# Shruthi-Analog-SMR4-mkII-v02.net
KiCad netlist of a schematic drawn in EAGLE
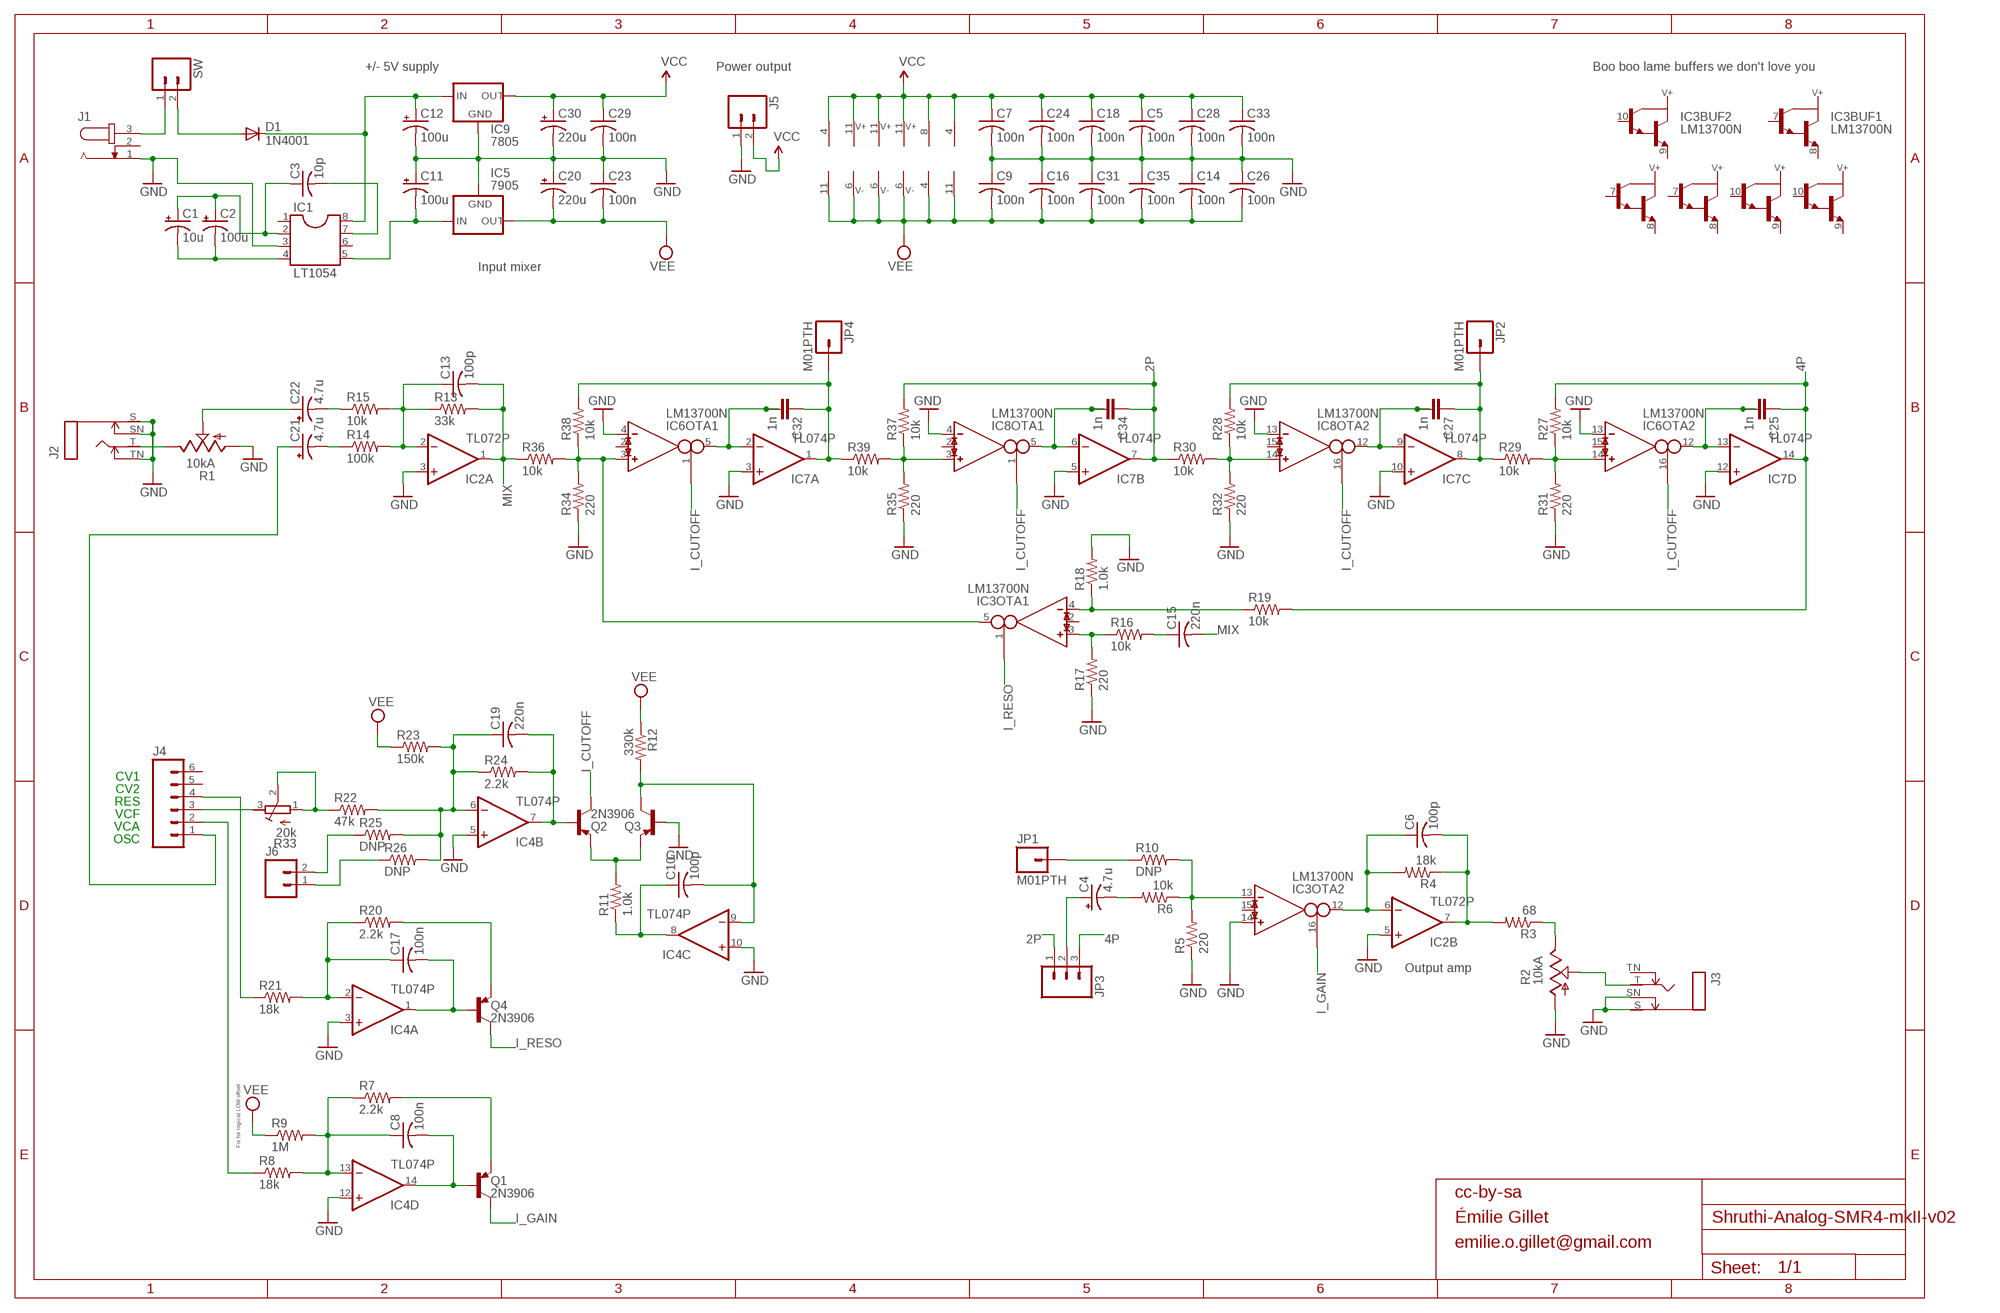
[diagram p0: schematic, sheet 1]

(export (version "E")
  (design (tool "Eeschema 10.0.6"))
  (components
    (comp (ref "C1")
      (value "10u")
      (footprint "eagle-import:E2,5-5")
      (libsource (lib "eagle-import") (part "CPOL-USE2.5-5"))
    )
    (comp (ref "C2")
      (value "100u")
      (footprint "eagle-import:E2,5-6")
      (libsource (lib "eagle-import") (part "CPOL-USE2.5-6"))
    )
    (comp (ref "C3")
      (value "10p")
      (footprint "eagle-import:C025-025X050")
      (libsource (lib "eagle-import") (part "C-US025-025X050"))
    )
    (comp (ref "C4")
      (value "4.7u")
      (footprint "eagle-import:E2,5-6")
      (libsource (lib "eagle-import") (part "CPOL-USE2.5-6"))
    )
    (comp (ref "C5")
      (value "100n")
      (footprint "eagle-import:C025-025X050")
      (libsource (lib "eagle-import") (part "C-US025-025X050"))
    )
    (comp (ref "C6")
      (value "100p")
      (footprint "eagle-import:C025-025X050")
      (libsource (lib "eagle-import") (part "C-US025-025X050"))
    )
    (comp (ref "C7")
      (value "100n")
      (footprint "eagle-import:C025-025X050")
      (libsource (lib "eagle-import") (part "C-US025-025X050"))
    )
    (comp (ref "C8")
      (value "100n")
      (footprint "eagle-import:C025-025X050")
      (libsource (lib "eagle-import") (part "C-US025-025X050"))
    )
    (comp (ref "C9")
      (value "100n")
      (footprint "eagle-import:C025-025X050")
      (libsource (lib "eagle-import") (part "C-US025-025X050"))
    )
    (comp (ref "C10")
      (value "100p")
      (footprint "eagle-import:C025-025X050")
      (libsource (lib "eagle-import") (part "C-US025-025X050"))
    )
    (comp (ref "C11")
      (value "100u")
      (footprint "eagle-import:E2,5-7")
      (libsource (lib "eagle-import") (part "CPOL-USE2.5-7"))
    )
    (comp (ref "C12")
      (value "100u")
      (footprint "eagle-import:E2,5-7")
      (libsource (lib "eagle-import") (part "CPOL-USE2.5-7"))
    )
    (comp (ref "C13")
      (value "100p")
      (footprint "eagle-import:C025-025X050")
      (libsource (lib "eagle-import") (part "C-US025-025X050"))
    )
    (comp (ref "C14")
      (value "100n")
      (footprint "eagle-import:C025-025X050")
      (libsource (lib "eagle-import") (part "C-US025-025X050"))
    )
    (comp (ref "C15")
      (value "220n")
      (footprint "eagle-import:C025-025X050")
      (libsource (lib "eagle-import") (part "C-US025-025X050"))
    )
    (comp (ref "C16")
      (value "100n")
      (footprint "eagle-import:C025-025X050")
      (libsource (lib "eagle-import") (part "C-US025-025X050"))
    )
    (comp (ref "C17")
      (value "100n")
      (footprint "eagle-import:C025-025X050")
      (libsource (lib "eagle-import") (part "C-US025-025X050"))
    )
    (comp (ref "C18")
      (value "100n")
      (footprint "eagle-import:C025-025X050")
      (libsource (lib "eagle-import") (part "C-US025-025X050"))
    )
    (comp (ref "C19")
      (value "220n")
      (footprint "eagle-import:C025-025X050")
      (libsource (lib "eagle-import") (part "C-US025-025X050"))
    )
    (comp (ref "C20")
      (value "220u")
      (footprint "eagle-import:E5-10,5")
      (libsource (lib "eagle-import") (part "CPOL-USE5-10.5"))
    )
    (comp (ref "C21")
      (value "4.7u")
      (footprint "eagle-import:E2,5-6")
      (libsource (lib "eagle-import") (part "CPOL-USE2.5-6"))
    )
    (comp (ref "C22")
      (value "4.7u")
      (footprint "eagle-import:E2,5-6")
      (libsource (lib "eagle-import") (part "CPOL-USE2.5-6"))
    )
    (comp (ref "C23")
      (value "100n")
      (footprint "eagle-import:C025-025X050")
      (libsource (lib "eagle-import") (part "C-US025-025X050"))
    )
    (comp (ref "C24")
      (value "100n")
      (footprint "eagle-import:C025-025X050")
      (libsource (lib "eagle-import") (part "C-US025-025X050"))
    )
    (comp (ref "C25")
      (value "1n")
      (footprint "eagle-import:C2.5_5-2")
      (libsource (lib "eagle-import") (part "C-2.5-5/2"))
    )
    (comp (ref "C26")
      (value "100n")
      (footprint "eagle-import:C025-025X050")
      (libsource (lib "eagle-import") (part "C-US025-025X050"))
    )
    (comp (ref "C27")
      (value "1n")
      (footprint "eagle-import:C2.5_5-2")
      (libsource (lib "eagle-import") (part "C-2.5-5/2"))
    )
    (comp (ref "C28")
      (value "100n")
      (footprint "eagle-import:C025-025X050")
      (libsource (lib "eagle-import") (part "C-US025-025X050"))
    )
    (comp (ref "C29")
      (value "100n")
      (footprint "eagle-import:C025-025X050")
      (libsource (lib "eagle-import") (part "C-US025-025X050"))
    )
    (comp (ref "C30")
      (value "220u")
      (footprint "eagle-import:E5-10,5")
      (libsource (lib "eagle-import") (part "CPOL-USE5-10.5"))
    )
    (comp (ref "C31")
      (value "100n")
      (footprint "eagle-import:C025-025X050")
      (libsource (lib "eagle-import") (part "C-US025-025X050"))
    )
    (comp (ref "C32")
      (value "1n")
      (footprint "eagle-import:C2.5_5-2")
      (libsource (lib "eagle-import") (part "C-2.5-5/2"))
    )
    (comp (ref "C33")
      (value "100n")
      (footprint "eagle-import:C025-025X050")
      (libsource (lib "eagle-import") (part "C-US025-025X050"))
    )
    (comp (ref "C34")
      (value "1n")
      (footprint "eagle-import:C2.5_5-2")
      (libsource (lib "eagle-import") (part "C-2.5-5/2"))
    )
    (comp (ref "C35")
      (value "100n")
      (footprint "eagle-import:C025-025X050")
      (libsource (lib "eagle-import") (part "C-US025-025X050"))
    )
    (comp (ref "D1")
      (value "1N4001")
      (footprint "eagle-import:DO41-10")
      (libsource (lib "eagle-import") (part "1N4004"))
    )
    (comp (ref "IC1")
      (value "LT1054")
      (footprint "eagle-import:DIL08")
      (libsource (lib "eagle-import") (part "DIL8"))
    )
    (comp (ref "IC2")
      (value "TL072P")
      (footprint "eagle-import:DIL08")
      (libsource (lib "eagle-import") (part "TL072P"))
    )
    (comp (ref "IC3")
      (value "LM13700N")
      (footprint "eagle-import:DIL16")
      (libsource (lib "eagle-import") (part "LM13700N"))
    )
    (comp (ref "IC4")
      (value "TL074P")
      (footprint "eagle-import:DIL14")
      (libsource (lib "eagle-import") (part "TL084P"))
    )
    (comp (ref "IC5")
      (value "7905")
      (footprint "eagle-import:79XXS")
      (libsource (lib "eagle-import") (part "79XXS"))
    )
    (comp (ref "IC6")
      (value "LM13700N")
      (footprint "eagle-import:DIL16")
      (libsource (lib "eagle-import") (part "LM13700N"))
    )
    (comp (ref "IC7")
      (value "TL074P")
      (footprint "eagle-import:DIL14")
      (libsource (lib "eagle-import") (part "TL084P"))
    )
    (comp (ref "IC8")
      (value "LM13700N")
      (footprint "eagle-import:DIL16")
      (libsource (lib "eagle-import") (part "LM13700N"))
    )
    (comp (ref "IC9")
      (value "7805")
      (footprint "eagle-import:78XXS")
      (libsource (lib "eagle-import") (part "78XXS"))
    )
    (comp (ref "J1")
      (value "JACK-PLUG2")
      (footprint "eagle-import:SPC4078_BIG_HOLES")
      (libsource (lib "eagle-import") (part "JACK-PLUG2"))
    )
    (comp (ref "J2")
      (value "MONOSWS")
      (footprint "eagle-import:NMJ4HC-S")
      (libsource (lib "eagle-import") (part "MONOSWS"))
    )
    (comp (ref "J3")
      (value "MONOSWS")
      (footprint "eagle-import:NMJ4HC-S")
      (libsource (lib "eagle-import") (part "MONOSWS"))
    )
    (comp (ref "J4")
      (value "M06SIP")
      (footprint "eagle-import:1X06")
      (libsource (lib "eagle-import") (part "M06SIP"))
    )
    (comp (ref "J5")
      (value "M02PTH")
      (footprint "eagle-import:1X02")
      (libsource (lib "eagle-import") (part "M02PTH"))
    )
    (comp (ref "J6")
      (value "M02PTH")
      (footprint "eagle-import:1X02")
      (libsource (lib "eagle-import") (part "M02PTH"))
    )
    (comp (ref "JP1")
      (value "M01PTH")
      (footprint "eagle-import:1X01")
      (libsource (lib "eagle-import") (part "M01PTH"))
    )
    (comp (ref "JP2")
      (value "M01PTH")
      (footprint "eagle-import:1X01")
      (libsource (lib "eagle-import") (part "M01PTH"))
    )
    (comp (ref "JP3")
      (value "M03PTH")
      (footprint "eagle-import:1X03")
      (libsource (lib "eagle-import") (part "M03PTH"))
    )
    (comp (ref "JP4")
      (value "M01PTH")
      (footprint "eagle-import:1X01")
      (libsource (lib "eagle-import") (part "M01PTH"))
    )
    (comp (ref "Q1")
      (value "2N3906")
      (footprint "eagle-import:TO92-")
      (libsource (lib "eagle-import") (part "2N3906-"))
    )
    (comp (ref "Q2")
      (value "2N3906")
      (footprint "eagle-import:TO92-")
      (libsource (lib "eagle-import") (part "2N3906-"))
    )
    (comp (ref "Q3")
      (value "2N3906")
      (footprint "eagle-import:TO92-")
      (libsource (lib "eagle-import") (part "2N3906-"))
    )
    (comp (ref "Q4")
      (value "2N3906")
      (footprint "eagle-import:TO92-")
      (libsource (lib "eagle-import") (part "2N3906-"))
    )
    (comp (ref "R1")
      (value "10kA")
      (footprint "eagle-import:CABLE_POT_6MM")
      (libsource (lib "eagle-import") (part "POT_USCABLED"))
    )
    (comp (ref "R2")
      (value "10kA")
      (footprint "eagle-import:CABLE_POT_6MM")
      (libsource (lib "eagle-import") (part "POT_USCABLED"))
    )
    (comp (ref "R3")
      (value "68")
      (footprint "eagle-import:0204_7")
      (libsource (lib "eagle-import") (part "R-US_0204/7"))
    )
    (comp (ref "R4")
      (value "18k")
      (footprint "eagle-import:0204_7")
      (libsource (lib "eagle-import") (part "R-US_0204/7"))
    )
    (comp (ref "R5")
      (value "220")
      (footprint "eagle-import:0204_7")
      (libsource (lib "eagle-import") (part "R-US_0204/7"))
    )
    (comp (ref "R6")
      (value "10k")
      (footprint "eagle-import:0204_7")
      (libsource (lib "eagle-import") (part "R-US_0204/7"))
    )
    (comp (ref "R7")
      (value "2.2k")
      (footprint "eagle-import:0204_7")
      (libsource (lib "eagle-import") (part "R-US_0204/7"))
    )
    (comp (ref "R8")
      (value "18k")
      (footprint "eagle-import:0204_7")
      (libsource (lib "eagle-import") (part "R-US_0204/7"))
    )
    (comp (ref "R9")
      (value "1M")
      (footprint "eagle-import:0204_7")
      (libsource (lib "eagle-import") (part "R-US_0204/7"))
    )
    (comp (ref "R10")
      (value "DNP")
      (footprint "eagle-import:0204V")
      (libsource (lib "eagle-import") (part "R-US_0204/2V"))
    )
    (comp (ref "R11")
      (value "1.0k")
      (footprint "eagle-import:0204_7")
      (libsource (lib "eagle-import") (part "R-US_0204/7"))
    )
    (comp (ref "R12")
      (value "330k")
      (footprint "eagle-import:0204_7")
      (libsource (lib "eagle-import") (part "R-US_0204/7"))
    )
    (comp (ref "R13")
      (value "33k")
      (footprint "eagle-import:0204_7")
      (libsource (lib "eagle-import") (part "R-US_0204/7"))
    )
    (comp (ref "R14")
      (value "100k")
      (footprint "eagle-import:0204_7")
      (libsource (lib "eagle-import") (part "R-US_0204/7"))
    )
    (comp (ref "R15")
      (value "10k")
      (footprint "eagle-import:0204_7")
      (libsource (lib "eagle-import") (part "R-US_0204/7"))
    )
    (comp (ref "R16")
      (value "10k")
      (footprint "eagle-import:0204_7")
      (libsource (lib "eagle-import") (part "R-US_0204/7"))
    )
    (comp (ref "R17")
      (value "220")
      (footprint "eagle-import:0204_7")
      (libsource (lib "eagle-import") (part "R-US_0204/7"))
    )
    (comp (ref "R18")
      (value "1.0k")
      (footprint "eagle-import:0204_7")
      (libsource (lib "eagle-import") (part "R-US_0204/7"))
    )
    (comp (ref "R19")
      (value "10k")
      (footprint "eagle-import:0204_7")
      (libsource (lib "eagle-import") (part "R-US_0204/7"))
    )
    (comp (ref "R20")
      (value "2.2k")
      (footprint "eagle-import:0204_7")
      (libsource (lib "eagle-import") (part "R-US_0204/7"))
    )
    (comp (ref "R21")
      (value "18k")
      (footprint "eagle-import:0204_7")
      (libsource (lib "eagle-import") (part "R-US_0204/7"))
    )
    (comp (ref "R22")
      (value "47k")
      (footprint "eagle-import:0204_7")
      (libsource (lib "eagle-import") (part "R-US_0204/7"))
    )
    (comp (ref "R23")
      (value "150k")
      (footprint "eagle-import:0204_7")
      (libsource (lib "eagle-import") (part "R-US_0204/7"))
    )
    (comp (ref "R24")
      (value "2.2k")
      (footprint "eagle-import:0204_7")
      (libsource (lib "eagle-import") (part "R-US_0204/7"))
    )
    (comp (ref "R25")
      (value "DNP")
      (footprint "eagle-import:0204V")
      (libsource (lib "eagle-import") (part "R-US_0204/2V"))
    )
    (comp (ref "R26")
      (value "DNP")
      (footprint "eagle-import:0204V")
      (libsource (lib "eagle-import") (part "R-US_0204/2V"))
    )
    (comp (ref "R27")
      (value "10k")
      (footprint "eagle-import:0204_7")
      (libsource (lib "eagle-import") (part "R-US_0204/7"))
    )
    (comp (ref "R28")
      (value "10k")
      (footprint "eagle-import:0204_7")
      (libsource (lib "eagle-import") (part "R-US_0204/7"))
    )
    (comp (ref "R29")
      (value "10k")
      (footprint "eagle-import:0204_7")
      (libsource (lib "eagle-import") (part "R-US_0204/7"))
    )
    (comp (ref "R30")
      (value "10k")
      (footprint "eagle-import:0204_7")
      (libsource (lib "eagle-import") (part "R-US_0204/7"))
    )
    (comp (ref "R31")
      (value "220")
      (footprint "eagle-import:0204_7")
      (libsource (lib "eagle-import") (part "R-US_0204/7"))
    )
    (comp (ref "R32")
      (value "220")
      (footprint "eagle-import:0204_7")
      (libsource (lib "eagle-import") (part "R-US_0204/7"))
    )
    (comp (ref "R33")
      (value "20k")
      (footprint "eagle-import:RTRIM3296X")
      (libsource (lib "eagle-import") (part "R-TRIMM3296X"))
    )
    (comp (ref "R34")
      (value "220")
      (footprint "eagle-import:0204_7")
      (libsource (lib "eagle-import") (part "R-US_0204/7"))
    )
    (comp (ref "R35")
      (value "220")
      (footprint "eagle-import:0204_7")
      (libsource (lib "eagle-import") (part "R-US_0204/7"))
    )
    (comp (ref "R36")
      (value "10k")
      (footprint "eagle-import:0204_7")
      (libsource (lib "eagle-import") (part "R-US_0204/7"))
    )
    (comp (ref "R37")
      (value "10k")
      (footprint "eagle-import:0204_7")
      (libsource (lib "eagle-import") (part "R-US_0204/7"))
    )
    (comp (ref "R38")
      (value "10k")
      (footprint "eagle-import:0204_7")
      (libsource (lib "eagle-import") (part "R-US_0204/7"))
    )
    (comp (ref "R39")
      (value "10k")
      (footprint "eagle-import:0204_7")
      (libsource (lib "eagle-import") (part "R-US_0204/7"))
    )
    (comp (ref "SW")
      (value "M02PTH")
      (footprint "eagle-import:1X02")
      (libsource (lib "eagle-import") (part "M02PTH"))
    )
  )
  (nets
    (net (code "1") (name "/2P") (class "Default")
      (node (ref "C34") (pin "1") (pinfunction "1_1") (pintype "passive"))
      (node (ref "IC7") (pin "7") (pinfunction "OUT_7") (pintype "output"))
      (node (ref "JP3") (pin "1") (pinfunction "1_1") (pintype "passive"))
      (node (ref "R30") (pin "1") (pinfunction "1_1") (pintype "passive"))
      (node (ref "R37") (pin "2") (pinfunction "2_2") (pintype "passive"))
    )
    (net (code "2") (name "/4P") (class "Default")
      (node (ref "C25") (pin "1") (pinfunction "1_1") (pintype "passive"))
      (node (ref "IC7") (pin "14") (pinfunction "OUT_14") (pintype "output"))
      (node (ref "JP3") (pin "3") (pinfunction "3_3") (pintype "passive"))
      (node (ref "R19") (pin "2") (pinfunction "2_2") (pintype "passive"))
      (node (ref "R27") (pin "2") (pinfunction "2_2") (pintype "passive"))
    )
    (net (code "3") (name "/I_CUTOFF") (class "Default")
      (node (ref "IC6") (pin "1") (pinfunction "I_BIAS_1") (pintype "input"))
      (node (ref "IC6") (pin "16") (pinfunction "I_BIAS_16") (pintype "input"))
      (node (ref "IC8") (pin "1") (pinfunction "I_BIAS_1") (pintype "input"))
      (node (ref "IC8") (pin "16") (pinfunction "I_BIAS_16") (pintype "input"))
      (node (ref "Q2") (pin "1") (pinfunction "C_1") (pintype "passive"))
    )
    (net (code "4") (name "/I_GAIN") (class "Default")
      (node (ref "IC3") (pin "16") (pinfunction "I_BIAS_16") (pintype "input"))
      (node (ref "Q1") (pin "1") (pinfunction "C_1") (pintype "passive"))
    )
    (net (code "5") (name "/I_RESO") (class "Default")
      (node (ref "IC3") (pin "1") (pinfunction "I_BIAS_1") (pintype "input"))
      (node (ref "Q4") (pin "1") (pinfunction "C_1") (pintype "passive"))
    )
    (net (code "6") (name "/MIX") (class "Default")
      (node (ref "C13") (pin "2") (pinfunction "2_2") (pintype "passive"))
      (node (ref "C15") (pin "2") (pinfunction "2_2") (pintype "passive"))
      (node (ref "IC2") (pin "1") (pinfunction "OUT_1") (pintype "output"))
      (node (ref "R13") (pin "2") (pinfunction "2_2") (pintype "passive"))
      (node (ref "R36") (pin "1") (pinfunction "1_1") (pintype "passive"))
    )
    (net (code "7") (name "GND") (class "Default")
      (node (ref "C11") (pin "+") (pinfunction "+_+") (pintype "passive"))
      (node (ref "C12") (pin "-") (pinfunction "-_-") (pintype "passive"))
      (node (ref "C14") (pin "1") (pinfunction "1_1") (pintype "passive"))
      (node (ref "C16") (pin "1") (pinfunction "1_1") (pintype "passive"))
      (node (ref "C18") (pin "2") (pinfunction "2_2") (pintype "passive"))
      (node (ref "C20") (pin "+") (pinfunction "+_+") (pintype "passive"))
      (node (ref "C23") (pin "1") (pinfunction "1_1") (pintype "passive"))
      (node (ref "C24") (pin "2") (pinfunction "2_2") (pintype "passive"))
      (node (ref "C26") (pin "1") (pinfunction "1_1") (pintype "passive"))
      (node (ref "C28") (pin "2") (pinfunction "2_2") (pintype "passive"))
      (node (ref "C29") (pin "2") (pinfunction "2_2") (pintype "passive"))
      (node (ref "C30") (pin "-") (pinfunction "-_-") (pintype "passive"))
      (node (ref "C31") (pin "1") (pinfunction "1_1") (pintype "passive"))
      (node (ref "C33") (pin "2") (pinfunction "2_2") (pintype "passive"))
      (node (ref "C35") (pin "1") (pinfunction "1_1") (pintype "passive"))
      (node (ref "C5") (pin "2") (pinfunction "2_2") (pintype "passive"))
      (node (ref "C7") (pin "2") (pinfunction "2_2") (pintype "passive"))
      (node (ref "C9") (pin "1") (pinfunction "1_1") (pintype "passive"))
      (node (ref "IC1") (pin "3") (pinfunction "3_3") (pintype "passive"))
      (node (ref "IC2") (pin "3") (pinfunction "+IN_3") (pintype "input"))
      (node (ref "IC2") (pin "5") (pinfunction "+IN_5") (pintype "input"))
      (node (ref "IC3") (pin "14") (pinfunction "IN_P_14") (pintype "input"))
      (node (ref "IC4") (pin "10") (pinfunction "+IN_10") (pintype "input"))
      (node (ref "IC4") (pin "12") (pinfunction "+IN_12") (pintype "input"))
      (node (ref "IC4") (pin "3") (pinfunction "+IN_3") (pintype "input"))
      (node (ref "IC4") (pin "5") (pinfunction "+IN_5") (pintype "input"))
      (node (ref "IC5") (pin "GND") (pinfunction "GND_GND") (pintype "input"))
      (node (ref "IC6") (pin "13") (pinfunction "IN_N_13") (pintype "input"))
      (node (ref "IC6") (pin "4") (pinfunction "IN_N_4") (pintype "input"))
      (node (ref "IC7") (pin "10") (pinfunction "+IN_10") (pintype "input"))
      (node (ref "IC7") (pin "12") (pinfunction "+IN_12") (pintype "input"))
      (node (ref "IC7") (pin "3") (pinfunction "+IN_3") (pintype "input"))
      (node (ref "IC7") (pin "5") (pinfunction "+IN_5") (pintype "input"))
      (node (ref "IC8") (pin "13") (pinfunction "IN_N_13") (pintype "input"))
      (node (ref "IC8") (pin "4") (pinfunction "IN_N_4") (pintype "input"))
      (node (ref "IC9") (pin "GND") (pinfunction "GND_GND") (pintype "input"))
      (node (ref "J1") (pin "1") (pinfunction "1_1") (pintype "passive"))
      (node (ref "J2") (pin "S") (pinfunction "S_S") (pintype "passive"))
      (node (ref "J2") (pin "SN") (pinfunction "SN_SN") (pintype "passive"))
      (node (ref "J2") (pin "TN") (pinfunction "TN_TN") (pintype "passive"))
      (node (ref "J3") (pin "S") (pinfunction "S_S") (pintype "passive"))
      (node (ref "J3") (pin "SN") (pinfunction "SN_SN") (pintype "passive"))
      (node (ref "J5") (pin "1") (pinfunction "1_1") (pintype "passive"))
      (node (ref "Q3") (pin "2") (pinfunction "B_2") (pintype "passive"))
      (node (ref "R1") (pin "A") (pinfunction "A_A") (pintype "passive"))
      (node (ref "R17") (pin "1") (pinfunction "1_1") (pintype "passive"))
      (node (ref "R18") (pin "2") (pinfunction "2_2") (pintype "passive"))
      (node (ref "R2") (pin "A") (pinfunction "A_A") (pintype "passive"))
      (node (ref "R31") (pin "1") (pinfunction "1_1") (pintype "passive"))
      (node (ref "R32") (pin "1") (pinfunction "1_1") (pintype "passive"))
      (node (ref "R34") (pin "1") (pinfunction "1_1") (pintype "passive"))
      (node (ref "R35") (pin "1") (pinfunction "1_1") (pintype "passive"))
      (node (ref "R5") (pin "1") (pinfunction "1_1") (pintype "passive"))
    )
    (net (code "8") (name "Net-(C1-Pad+)") (class "Default")
      (node (ref "C1") (pin "+") (pinfunction "+_+") (pintype "passive"))
      (node (ref "C2") (pin "+") (pinfunction "+_+") (pintype "passive"))
      (node (ref "C3") (pin "1") (pinfunction "1_1") (pintype "passive"))
      (node (ref "IC1") (pin "2") (pinfunction "2_2") (pintype "passive"))
    )
    (net (code "9") (name "Net-(C1-Pad-)") (class "Default")
      (node (ref "C1") (pin "-") (pinfunction "-_-") (pintype "passive"))
      (node (ref "C2") (pin "-") (pinfunction "-_-") (pintype "passive"))
      (node (ref "IC1") (pin "4") (pinfunction "4_4") (pintype "passive"))
    )
    (net (code "10") (name "Net-(C3-Pad2)") (class "Default")
      (node (ref "C3") (pin "2") (pinfunction "2_2") (pintype "passive"))
      (node (ref "IC1") (pin "7") (pinfunction "7_7") (pintype "passive"))
    )
    (net (code "11") (name "Net-(C4-Pad+)") (class "Default")
      (node (ref "C4") (pin "+") (pinfunction "+_+") (pintype "passive"))
      (node (ref "JP3") (pin "2") (pinfunction "2_2") (pintype "passive"))
    )
    (net (code "12") (name "Net-(C4-Pad-)") (class "Default")
      (node (ref "C4") (pin "-") (pinfunction "-_-") (pintype "passive"))
      (node (ref "R6") (pin "2") (pinfunction "2_2") (pintype "passive"))
    )
    (net (code "13") (name "Net-(C11-Pad-)") (class "Default")
      (node (ref "C11") (pin "-") (pinfunction "-_-") (pintype "passive"))
      (node (ref "IC1") (pin "5") (pinfunction "5_5") (pintype "passive"))
      (node (ref "IC5") (pin "IN") (pinfunction "IN_IN") (pintype "input"))
    )
    (net (code "14") (name "Net-(C12-Pad+)") (class "Default")
      (node (ref "C12") (pin "+") (pinfunction "+_+") (pintype "passive"))
      (node (ref "D1") (pin "C") (pinfunction "C_C") (pintype "passive"))
      (node (ref "IC1") (pin "8") (pinfunction "8_8") (pintype "passive"))
      (node (ref "IC9") (pin "IN") (pinfunction "IN_IN") (pintype "input"))
    )
    (net (code "15") (name "Net-(C15-Pad1)") (class "Default")
      (node (ref "C15") (pin "1") (pinfunction "1_1") (pintype "passive"))
      (node (ref "R16") (pin "2") (pinfunction "2_2") (pintype "passive"))
    )
    (net (code "16") (name "Net-(C21-Pad+)") (class "Default")
      (node (ref "C21") (pin "+") (pinfunction "+_+") (pintype "passive"))
      (node (ref "J4") (pin "1") (pinfunction "1_1") (pintype "passive"))
    )
    (net (code "17") (name "Net-(C21-Pad-)") (class "Default")
      (node (ref "C21") (pin "-") (pinfunction "-_-") (pintype "passive"))
      (node (ref "R14") (pin "1") (pinfunction "1_1") (pintype "passive"))
    )
    (net (code "18") (name "Net-(C22-Pad+)") (class "Default")
      (node (ref "C22") (pin "+") (pinfunction "+_+") (pintype "passive"))
      (node (ref "R1") (pin "S") (pinfunction "S_S") (pintype "passive"))
    )
    (net (code "19") (name "Net-(C22-Pad-)") (class "Default")
      (node (ref "C22") (pin "-") (pinfunction "-_-") (pintype "passive"))
      (node (ref "R15") (pin "1") (pinfunction "1_1") (pintype "passive"))
    )
    (net (code "20") (name "Net-(D1-PadA)") (class "Default")
      (node (ref "D1") (pin "A") (pinfunction "A_A") (pintype "passive"))
      (node (ref "SW") (pin "2") (pinfunction "2_2") (pintype "passive"))
    )
    (net (code "21") (name "Net-(IC2A--IN)") (class "Default")
      (node (ref "C13") (pin "1") (pinfunction "1_1") (pintype "passive"))
      (node (ref "IC2") (pin "2") (pinfunction "-IN_2") (pintype "input"))
      (node (ref "R13") (pin "1") (pinfunction "1_1") (pintype "passive"))
      (node (ref "R14") (pin "2") (pinfunction "2_2") (pintype "passive"))
      (node (ref "R15") (pin "2") (pinfunction "2_2") (pintype "passive"))
    )
    (net (code "22") (name "Net-(IC2B--IN)") (class "Default")
      (node (ref "C6") (pin "1") (pinfunction "1_1") (pintype "passive"))
      (node (ref "IC2") (pin "6") (pinfunction "-IN_6") (pintype "input"))
      (node (ref "IC3") (pin "12") (pinfunction "OUT_12") (pintype "output"))
      (node (ref "R4") (pin "2") (pinfunction "2_2") (pintype "passive"))
    )
    (net (code "23") (name "Net-(IC2B-OUT)") (class "Default")
      (node (ref "C6") (pin "2") (pinfunction "2_2") (pintype "passive"))
      (node (ref "IC2") (pin "7") (pinfunction "OUT_7") (pintype "output"))
      (node (ref "R3") (pin "2") (pinfunction "2_2") (pintype "passive"))
      (node (ref "R4") (pin "1") (pinfunction "1_1") (pintype "passive"))
    )
    (net (code "24") (name "Net-(IC3C-IN_N)") (class "Default")
      (node (ref "IC3") (pin "4") (pinfunction "IN_N_4") (pintype "input"))
      (node (ref "R18") (pin "1") (pinfunction "1_1") (pintype "passive"))
      (node (ref "R19") (pin "1") (pinfunction "1_1") (pintype "passive"))
    )
    (net (code "25") (name "Net-(IC3C-IN_P)") (class "Default")
      (node (ref "IC3") (pin "3") (pinfunction "IN_P_3") (pintype "input"))
      (node (ref "R16") (pin "1") (pinfunction "1_1") (pintype "passive"))
      (node (ref "R17") (pin "2") (pinfunction "2_2") (pintype "passive"))
    )
    (net (code "26") (name "Net-(IC3C-OUT)") (class "Default")
      (node (ref "IC3") (pin "5") (pinfunction "OUT_5") (pintype "output"))
      (node (ref "IC6") (pin "3") (pinfunction "IN_P_3") (pintype "input"))
      (node (ref "R34") (pin "2") (pinfunction "2_2") (pintype "passive"))
      (node (ref "R36") (pin "2") (pinfunction "2_2") (pintype "passive"))
      (node (ref "R38") (pin "1") (pinfunction "1_1") (pintype "passive"))
    )
    (net (code "27") (name "Net-(IC3D-IN_N)") (class "Default")
      (node (ref "IC3") (pin "13") (pinfunction "IN_N_13") (pintype "input"))
      (node (ref "R10") (pin "2") (pinfunction "2_2") (pintype "passive"))
      (node (ref "R5") (pin "2") (pinfunction "2_2") (pintype "passive"))
      (node (ref "R6") (pin "1") (pinfunction "1_1") (pintype "passive"))
    )
    (net (code "28") (name "Net-(IC4A--IN)") (class "Default")
      (node (ref "C17") (pin "1") (pinfunction "1_1") (pintype "passive"))
      (node (ref "IC4") (pin "2") (pinfunction "-IN_2") (pintype "input"))
      (node (ref "R20") (pin "1") (pinfunction "1_1") (pintype "passive"))
      (node (ref "R21") (pin "2") (pinfunction "2_2") (pintype "passive"))
    )
    (net (code "29") (name "Net-(IC4A-OUT)") (class "Default")
      (node (ref "C17") (pin "2") (pinfunction "2_2") (pintype "passive"))
      (node (ref "IC4") (pin "1") (pinfunction "OUT_1") (pintype "output"))
      (node (ref "Q4") (pin "2") (pinfunction "B_2") (pintype "passive"))
    )
    (net (code "30") (name "Net-(IC4B--IN)") (class "Default")
      (node (ref "C19") (pin "1") (pinfunction "1_1") (pintype "passive"))
      (node (ref "IC4") (pin "6") (pinfunction "-IN_6") (pintype "input"))
      (node (ref "R22") (pin "2") (pinfunction "2_2") (pintype "passive"))
      (node (ref "R23") (pin "2") (pinfunction "2_2") (pintype "passive"))
      (node (ref "R24") (pin "1") (pinfunction "1_1") (pintype "passive"))
      (node (ref "R25") (pin "2") (pinfunction "2_2") (pintype "passive"))
      (node (ref "R26") (pin "2") (pinfunction "2_2") (pintype "passive"))
    )
    (net (code "31") (name "Net-(IC4B-OUT)") (class "Default")
      (node (ref "C19") (pin "2") (pinfunction "2_2") (pintype "passive"))
      (node (ref "IC4") (pin "7") (pinfunction "OUT_7") (pintype "output"))
      (node (ref "Q2") (pin "2") (pinfunction "B_2") (pintype "passive"))
      (node (ref "R24") (pin "2") (pinfunction "2_2") (pintype "passive"))
    )
    (net (code "32") (name "Net-(IC4C--IN)") (class "Default")
      (node (ref "C10") (pin "2") (pinfunction "2_2") (pintype "passive"))
      (node (ref "IC4") (pin "9") (pinfunction "-IN_9") (pintype "input"))
      (node (ref "Q3") (pin "1") (pinfunction "C_1") (pintype "passive"))
      (node (ref "R12") (pin "2") (pinfunction "2_2") (pintype "passive"))
    )
    (net (code "33") (name "Net-(IC4C-OUT)") (class "Default")
      (node (ref "C10") (pin "1") (pinfunction "1_1") (pintype "passive"))
      (node (ref "IC4") (pin "8") (pinfunction "OUT_8") (pintype "output"))
      (node (ref "R11") (pin "1") (pinfunction "1_1") (pintype "passive"))
    )
    (net (code "34") (name "Net-(IC4D--IN)") (class "Default")
      (node (ref "C8") (pin "1") (pinfunction "1_1") (pintype "passive"))
      (node (ref "IC4") (pin "13") (pinfunction "-IN_13") (pintype "input"))
      (node (ref "R7") (pin "1") (pinfunction "1_1") (pintype "passive"))
      (node (ref "R8") (pin "2") (pinfunction "2_2") (pintype "passive"))
      (node (ref "R9") (pin "2") (pinfunction "2_2") (pintype "passive"))
    )
    (net (code "35") (name "Net-(IC4D-OUT)") (class "Default")
      (node (ref "C8") (pin "2") (pinfunction "2_2") (pintype "passive"))
      (node (ref "IC4") (pin "14") (pinfunction "OUT_14") (pintype "output"))
      (node (ref "Q1") (pin "2") (pinfunction "B_2") (pintype "passive"))
    )
    (net (code "36") (name "Net-(IC6C-OUT)") (class "Default")
      (node (ref "C32") (pin "2") (pinfunction "2_2") (pintype "passive"))
      (node (ref "C32") (pin "3") (pinfunction "3_3") (pintype "passive"))
      (node (ref "IC6") (pin "5") (pinfunction "OUT_5") (pintype "output"))
      (node (ref "IC7") (pin "2") (pinfunction "-IN_2") (pintype "input"))
    )
    (net (code "37") (name "Net-(IC6D-IN_P)") (class "Default")
      (node (ref "IC6") (pin "14") (pinfunction "IN_P_14") (pintype "input"))
      (node (ref "R27") (pin "1") (pinfunction "1_1") (pintype "passive"))
      (node (ref "R29") (pin "2") (pinfunction "2_2") (pintype "passive"))
      (node (ref "R31") (pin "2") (pinfunction "2_2") (pintype "passive"))
    )
    (net (code "38") (name "Net-(IC6D-OUT)") (class "Default")
      (node (ref "C25") (pin "2") (pinfunction "2_2") (pintype "passive"))
      (node (ref "C25") (pin "3") (pinfunction "3_3") (pintype "passive"))
      (node (ref "IC6") (pin "12") (pinfunction "OUT_12") (pintype "output"))
      (node (ref "IC7") (pin "13") (pinfunction "-IN_13") (pintype "input"))
    )
    (net (code "39") (name "Net-(IC7A-OUT)") (class "Default")
      (node (ref "C32") (pin "1") (pinfunction "1_1") (pintype "passive"))
      (node (ref "IC7") (pin "1") (pinfunction "OUT_1") (pintype "output"))
      (node (ref "JP4") (pin "1") (pinfunction "1_1") (pintype "passive"))
      (node (ref "R38") (pin "2") (pinfunction "2_2") (pintype "passive"))
      (node (ref "R39") (pin "1") (pinfunction "1_1") (pintype "passive"))
    )
    (net (code "40") (name "Net-(IC7B--IN)") (class "Default")
      (node (ref "C34") (pin "2") (pinfunction "2_2") (pintype "passive"))
      (node (ref "C34") (pin "3") (pinfunction "3_3") (pintype "passive"))
      (node (ref "IC7") (pin "6") (pinfunction "-IN_6") (pintype "input"))
      (node (ref "IC8") (pin "5") (pinfunction "OUT_5") (pintype "output"))
    )
    (net (code "41") (name "Net-(IC7C--IN)") (class "Default")
      (node (ref "C27") (pin "2") (pinfunction "2_2") (pintype "passive"))
      (node (ref "C27") (pin "3") (pinfunction "3_3") (pintype "passive"))
      (node (ref "IC7") (pin "9") (pinfunction "-IN_9") (pintype "input"))
      (node (ref "IC8") (pin "12") (pinfunction "OUT_12") (pintype "output"))
    )
    (net (code "42") (name "Net-(IC7C-OUT)") (class "Default")
      (node (ref "C27") (pin "1") (pinfunction "1_1") (pintype "passive"))
      (node (ref "IC7") (pin "8") (pinfunction "OUT_8") (pintype "output"))
      (node (ref "JP2") (pin "1") (pinfunction "1_1") (pintype "passive"))
      (node (ref "R28") (pin "2") (pinfunction "2_2") (pintype "passive"))
      (node (ref "R29") (pin "1") (pinfunction "1_1") (pintype "passive"))
    )
    (net (code "43") (name "Net-(IC8C-IN_P)") (class "Default")
      (node (ref "IC8") (pin "3") (pinfunction "IN_P_3") (pintype "input"))
      (node (ref "R35") (pin "2") (pinfunction "2_2") (pintype "passive"))
      (node (ref "R37") (pin "1") (pinfunction "1_1") (pintype "passive"))
      (node (ref "R39") (pin "2") (pinfunction "2_2") (pintype "passive"))
    )
    (net (code "44") (name "Net-(IC8D-IN_P)") (class "Default")
      (node (ref "IC8") (pin "14") (pinfunction "IN_P_14") (pintype "input"))
      (node (ref "R28") (pin "1") (pinfunction "1_1") (pintype "passive"))
      (node (ref "R30") (pin "2") (pinfunction "2_2") (pintype "passive"))
      (node (ref "R32") (pin "2") (pinfunction "2_2") (pintype "passive"))
    )
    (net (code "45") (name "Net-(J1-Pad3)") (class "Default")
      (node (ref "J1") (pin "3") (pinfunction "3_3") (pintype "passive"))
      (node (ref "SW") (pin "1") (pinfunction "1_1") (pintype "passive"))
    )
    (net (code "46") (name "Net-(J2-PadT)") (class "Default")
      (node (ref "J2") (pin "T") (pinfunction "T_T") (pintype "passive"))
      (node (ref "R1") (pin "E") (pinfunction "E_E") (pintype "passive"))
    )
    (net (code "47") (name "Net-(J3-PadT)") (class "Default")
      (node (ref "J3") (pin "T") (pinfunction "T_T") (pintype "passive"))
      (node (ref "R2") (pin "S") (pinfunction "S_S") (pintype "passive"))
    )
    (net (code "48") (name "Net-(J4-Pad2)") (class "Default")
      (node (ref "J4") (pin "2") (pinfunction "2_2") (pintype "passive"))
      (node (ref "R8") (pin "1") (pinfunction "1_1") (pintype "passive"))
    )
    (net (code "49") (name "Net-(J4-Pad4)") (class "Default")
      (node (ref "J4") (pin "4") (pinfunction "4_4") (pintype "passive"))
      (node (ref "R21") (pin "1") (pinfunction "1_1") (pintype "passive"))
    )
    (net (code "50") (name "Net-(J6-Pad1)") (class "Default")
      (node (ref "J6") (pin "1") (pinfunction "1_1") (pintype "passive"))
      (node (ref "R26") (pin "1") (pinfunction "1_1") (pintype "passive"))
    )
    (net (code "51") (name "Net-(J6-Pad2)") (class "Default")
      (node (ref "J6") (pin "2") (pinfunction "2_2") (pintype "passive"))
      (node (ref "R25") (pin "1") (pinfunction "1_1") (pintype "passive"))
    )
    (net (code "52") (name "Net-(JP1-Pad1)") (class "Default")
      (node (ref "JP1") (pin "1") (pinfunction "1_1") (pintype "passive"))
      (node (ref "R10") (pin "1") (pinfunction "1_1") (pintype "passive"))
    )
    (net (code "53") (name "Net-(Q1-E)") (class "Default")
      (node (ref "Q1") (pin "3") (pinfunction "E_3") (pintype "passive"))
      (node (ref "R7") (pin "2") (pinfunction "2_2") (pintype "passive"))
    )
    (net (code "54") (name "Net-(Q2-E)") (class "Default")
      (node (ref "Q2") (pin "3") (pinfunction "E_3") (pintype "passive"))
      (node (ref "Q3") (pin "3") (pinfunction "E_3") (pintype "passive"))
      (node (ref "R11") (pin "2") (pinfunction "2_2") (pintype "passive"))
    )
    (net (code "55") (name "Net-(Q4-E)") (class "Default")
      (node (ref "Q4") (pin "3") (pinfunction "E_3") (pintype "passive"))
      (node (ref "R20") (pin "2") (pinfunction "2_2") (pintype "passive"))
    )
    (net (code "56") (name "Net-(R2-PadE)") (class "Default")
      (node (ref "R2") (pin "E") (pinfunction "E_E") (pintype "passive"))
      (node (ref "R3") (pin "1") (pinfunction "1_1") (pintype "passive"))
    )
    (net (code "57") (name "Net-(R33-A)") (class "Default")
      (node (ref "J4") (pin "3") (pinfunction "3_3") (pintype "passive"))
      (node (ref "R33") (pin "3") (pinfunction "A_3") (pintype "passive"))
    )
    (net (code "58") (name "Net-(R33-E)") (class "Default")
      (node (ref "R22") (pin "1") (pinfunction "1_1") (pintype "passive"))
      (node (ref "R33") (pin "1") (pinfunction "E_1") (pintype "passive"))
      (node (ref "R33") (pin "2") (pinfunction "S_2") (pintype "passive"))
    )
    (net (code "59") (name "VCC") (class "Default")
      (node (ref "C18") (pin "1") (pinfunction "1_1") (pintype "passive"))
      (node (ref "C24") (pin "1") (pinfunction "1_1") (pintype "passive"))
      (node (ref "C28") (pin "1") (pinfunction "1_1") (pintype "passive"))
      (node (ref "C29") (pin "1") (pinfunction "1_1") (pintype "passive"))
      (node (ref "C30") (pin "+") (pinfunction "+_+") (pintype "passive"))
      (node (ref "C33") (pin "1") (pinfunction "1_1") (pintype "passive"))
      (node (ref "C5") (pin "1") (pinfunction "1_1") (pintype "passive"))
      (node (ref "C7") (pin "1") (pinfunction "1_1") (pintype "passive"))
      (node (ref "IC2") (pin "8") (pinfunction "V+_8") (pintype "power_in"))
      (node (ref "IC3") (pin "11") (pinfunction "V+_11") (pintype "power_in"))
      (node (ref "IC4") (pin "4") (pinfunction "V+_4") (pintype "power_in"))
      (node (ref "IC6") (pin "11") (pinfunction "V+_11") (pintype "power_in"))
      (node (ref "IC7") (pin "4") (pinfunction "V+_4") (pintype "power_in"))
      (node (ref "IC8") (pin "11") (pinfunction "V+_11") (pintype "power_in"))
      (node (ref "IC9") (pin "OUT") (pinfunction "OUT_OUT") (pintype "passive"))
      (node (ref "J5") (pin "2") (pinfunction "2_2") (pintype "passive"))
    )
    (net (code "60") (name "VEE") (class "Default")
      (node (ref "C14") (pin "2") (pinfunction "2_2") (pintype "passive"))
      (node (ref "C16") (pin "2") (pinfunction "2_2") (pintype "passive"))
      (node (ref "C20") (pin "-") (pinfunction "-_-") (pintype "passive"))
      (node (ref "C23") (pin "2") (pinfunction "2_2") (pintype "passive"))
      (node (ref "C26") (pin "2") (pinfunction "2_2") (pintype "passive"))
      (node (ref "C31") (pin "2") (pinfunction "2_2") (pintype "passive"))
      (node (ref "C35") (pin "2") (pinfunction "2_2") (pintype "passive"))
      (node (ref "C9") (pin "2") (pinfunction "2_2") (pintype "passive"))
      (node (ref "IC2") (pin "4") (pinfunction "V-_4") (pintype "power_in"))
      (node (ref "IC3") (pin "6") (pinfunction "V-_6") (pintype "power_in"))
      (node (ref "IC4") (pin "11") (pinfunction "V-_11") (pintype "power_in"))
      (node (ref "IC5") (pin "OUT") (pinfunction "OUT_OUT") (pintype "passive"))
      (node (ref "IC6") (pin "6") (pinfunction "V-_6") (pintype "power_in"))
      (node (ref "IC7") (pin "11") (pinfunction "V-_11") (pintype "power_in"))
      (node (ref "IC8") (pin "6") (pinfunction "V-_6") (pintype "power_in"))
      (node (ref "R12") (pin "1") (pinfunction "1_1") (pintype "passive"))
      (node (ref "R23") (pin "1") (pinfunction "1_1") (pintype "passive"))
      (node (ref "R9") (pin "1") (pinfunction "1_1") (pintype "passive"))
    )
    (net (code "61") (name "unconnected-(IC1-Pad1)") (class "Default")
      (node (ref "IC1") (pin "1") (pinfunction "1_1") (pintype "passive"))
    )
    (net (code "62") (name "unconnected-(IC1-Pad6)") (class "Default")
      (node (ref "IC1") (pin "6") (pinfunction "6_6") (pintype "passive"))
    )
    (net (code "63") (name "unconnected-(IC3A-B-Pad7)") (class "Default")
      (node (ref "IC3") (pin "7") (pinfunction "B_7") (pintype "passive"))
    )
    (net (code "64") (name "unconnected-(IC3A-E-Pad8)") (class "Default")
      (node (ref "IC3") (pin "8") (pinfunction "E_8") (pintype "passive"))
    )
    (net (code "65") (name "unconnected-(IC3B-B-Pad10)") (class "Default")
      (node (ref "IC3") (pin "10") (pinfunction "B_10") (pintype "passive"))
    )
    (net (code "66") (name "unconnected-(IC3B-E-Pad9)") (class "Default")
      (node (ref "IC3") (pin "9") (pinfunction "E_9") (pintype "passive"))
    )
    (net (code "67") (name "unconnected-(IC3C-I_DIODE-Pad2)") (class "Default")
      (node (ref "IC3") (pin "2") (pinfunction "I_DIODE_2") (pintype "input"))
    )
    (net (code "68") (name "unconnected-(IC3D-I_DIODE-Pad15)") (class "Default")
      (node (ref "IC3") (pin "15") (pinfunction "I_DIODE_15") (pintype "input"))
    )
    (net (code "69") (name "unconnected-(IC6A-B-Pad7)") (class "Default")
      (node (ref "IC6") (pin "7") (pinfunction "B_7") (pintype "passive"))
    )
    (net (code "70") (name "unconnected-(IC6A-E-Pad8)") (class "Default")
      (node (ref "IC6") (pin "8") (pinfunction "E_8") (pintype "passive"))
    )
    (net (code "71") (name "unconnected-(IC6B-B-Pad10)") (class "Default")
      (node (ref "IC6") (pin "10") (pinfunction "B_10") (pintype "passive"))
    )
    (net (code "72") (name "unconnected-(IC6B-E-Pad9)") (class "Default")
      (node (ref "IC6") (pin "9") (pinfunction "E_9") (pintype "passive"))
    )
    (net (code "73") (name "unconnected-(IC6C-I_DIODE-Pad2)") (class "Default")
      (node (ref "IC6") (pin "2") (pinfunction "I_DIODE_2") (pintype "input"))
    )
    (net (code "74") (name "unconnected-(IC6D-I_DIODE-Pad15)") (class "Default")
      (node (ref "IC6") (pin "15") (pinfunction "I_DIODE_15") (pintype "input"))
    )
    (net (code "75") (name "unconnected-(IC8A-B-Pad7)") (class "Default")
      (node (ref "IC8") (pin "7") (pinfunction "B_7") (pintype "passive"))
    )
    (net (code "76") (name "unconnected-(IC8A-E-Pad8)") (class "Default")
      (node (ref "IC8") (pin "8") (pinfunction "E_8") (pintype "passive"))
    )
    (net (code "77") (name "unconnected-(IC8B-B-Pad10)") (class "Default")
      (node (ref "IC8") (pin "10") (pinfunction "B_10") (pintype "passive"))
    )
    (net (code "78") (name "unconnected-(IC8B-E-Pad9)") (class "Default")
      (node (ref "IC8") (pin "9") (pinfunction "E_9") (pintype "passive"))
    )
    (net (code "79") (name "unconnected-(IC8C-I_DIODE-Pad2)") (class "Default")
      (node (ref "IC8") (pin "2") (pinfunction "I_DIODE_2") (pintype "input"))
    )
    (net (code "80") (name "unconnected-(IC8D-I_DIODE-Pad15)") (class "Default")
      (node (ref "IC8") (pin "15") (pinfunction "I_DIODE_15") (pintype "input"))
    )
    (net (code "81") (name "unconnected-(J1-Pad2)") (class "Default")
      (node (ref "J1") (pin "2") (pinfunction "2_2") (pintype "passive"))
    )
    (net (code "82") (name "unconnected-(J3-PadTN)") (class "Default")
      (node (ref "J3") (pin "TN") (pinfunction "TN_TN") (pintype "passive"))
    )
    (net (code "83") (name "unconnected-(J4-Pad5)") (class "Default")
      (node (ref "J4") (pin "5") (pinfunction "5_5") (pintype "passive"))
    )
    (net (code "84") (name "unconnected-(J4-Pad6)") (class "Default")
      (node (ref "J4") (pin "6") (pinfunction "6_6") (pintype "passive"))
    )
  )
)
